# PD_Sche.net
KiCad netlist of a schematic drawn in Altium Designer
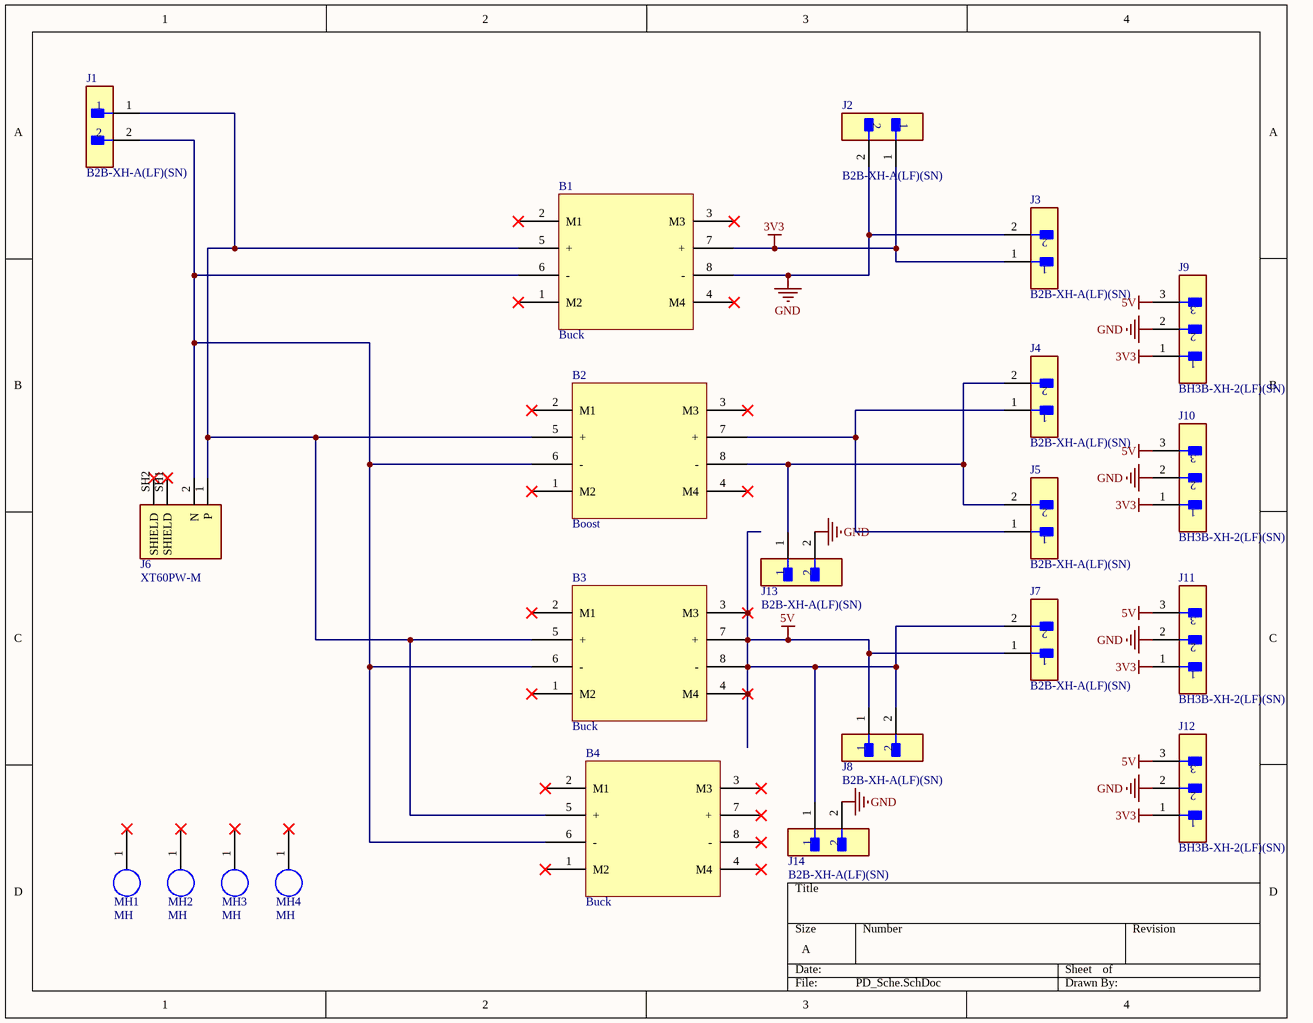
[diagram p0: PD_Sche.SchDoc]

(export (version "E")
  (design (tool "Eeschema 10.0.6"))
  (components
    (comp (ref "B1") (value "Buck") (footprint "Buck") (libsource (lib "PD_sym") (part "Buck")))
    (comp (ref "B2") (value "Boost") (footprint "Boost") (libsource (lib "PD_sym") (part "Boost")))
    (comp (ref "B3") (value "Buck") (footprint "Buck") (libsource (lib "PD_sym") (part "Buck")))
    (comp (ref "B4") (value "Buck") (footprint "Buck") (libsource (lib "PD_sym") (part "Buck")))
    (comp (ref "J1")
      (value "B2B-XH-A(LF)(SN)")
      (footprint "FP-B2B-XH-A_LF_SN-MFG")
      (description "CONN HEADER VERT 2POS 2.5MM")
      (libsource (lib "") (part "3bc925449376181038e59eaffc5286c_2"))
    )
    (comp (ref "J2")
      (value "B2B-XH-A(LF)(SN)")
      (footprint "FP-B2B-XH-A_LF_SN-MFG")
      (description "CONN HEADER VERT 2POS 2.5MM")
      (libsource (lib "") (part "3bc925449376181038e59eaffc5286c_3"))
    )
    (comp (ref "J3")
      (value "B2B-XH-A(LF)(SN)")
      (footprint "FP-B2B-XH-A_LF_SN-MFG")
      (description "CONN HEADER VERT 2POS 2.5MM")
      (libsource (lib "Altium Content Vault") (part "3bc925449376181038e59eaffc5286c"))
    )
    (comp (ref "J4")
      (value "B2B-XH-A(LF)(SN)")
      (footprint "FP-B2B-XH-A_LF_SN-MFG")
      (description "CONN HEADER VERT 2POS 2.5MM")
      (libsource (lib "Altium Content Vault") (part "3bc925449376181038e59eaffc5286c"))
    )
    (comp (ref "J5")
      (value "B2B-XH-A(LF)(SN)")
      (footprint "FP-B2B-XH-A_LF_SN-MFG")
      (description "CONN HEADER VERT 2POS 2.5MM")
      (libsource (lib "Altium Content Vault") (part "3bc925449376181038e59eaffc5286c"))
    )
    (comp (ref "J6")
      (value "XT60PW-M")
      (footprint "AMASS_XT60PW-M")
      (description "Socket, DC supply, male, PIN: 2")
      (fields (field (name "MF") "AMASS"))
      (libsource (lib "PD_sym") (part "XT60PW-M"))
    )
    (comp (ref "J7")
      (value "B2B-XH-A(LF)(SN)")
      (footprint "FP-B2B-XH-A_LF_SN-MFG")
      (description "CONN HEADER VERT 2POS 2.5MM")
      (libsource (lib "Altium Content Vault") (part "3bc925449376181038e59eaffc5286c"))
    )
    (comp (ref "J8")
      (value "B2B-XH-A(LF)(SN)")
      (footprint "FP-B2B-XH-A_LF_SN-MFG")
      (description "CONN HEADER VERT 2POS 2.5MM")
      (libsource (lib "") (part "3bc925449376181038e59eaffc5286c_1"))
    )
    (comp (ref "J9")
      (value "BH3B-XH-2(LF)(SN)")
      (footprint "FP-BH3B-XH-2_LF_SN-MFG")
      (description "CONN HEADER VERT 3POS 2.5MM")
      (libsource (lib "Altium Content Vault") (part "0d3f023dd272f625e17a2be33dea85f"))
    )
    (comp (ref "J10")
      (value "BH3B-XH-2(LF)(SN)")
      (footprint "FP-BH3B-XH-2_LF_SN-MFG")
      (description "CONN HEADER VERT 3POS 2.5MM")
      (libsource (lib "Altium Content Vault") (part "0d3f023dd272f625e17a2be33dea85f"))
    )
    (comp (ref "J11")
      (value "BH3B-XH-2(LF)(SN)")
      (footprint "FP-BH3B-XH-2_LF_SN-MFG")
      (description "CONN HEADER VERT 3POS 2.5MM")
      (libsource (lib "Altium Content Vault") (part "0d3f023dd272f625e17a2be33dea85f"))
    )
    (comp (ref "J12")
      (value "BH3B-XH-2(LF)(SN)")
      (footprint "FP-BH3B-XH-2_LF_SN-MFG")
      (description "CONN HEADER VERT 3POS 2.5MM")
      (libsource (lib "Altium Content Vault") (part "0d3f023dd272f625e17a2be33dea85f"))
    )
    (comp (ref "J13")
      (value "B2B-XH-A(LF)(SN)")
      (footprint "FP-B2B-XH-A_LF_SN-MFG")
      (description "CONN HEADER VERT 2POS 2.5MM")
      (libsource (lib "") (part "3bc925449376181038e59eaffc5286c_1"))
    )
    (comp (ref "J14")
      (value "B2B-XH-A(LF)(SN)")
      (footprint "FP-B2B-XH-A_LF_SN-MFG")
      (description "CONN HEADER VERT 2POS 2.5MM")
      (libsource (lib "") (part "3bc925449376181038e59eaffc5286c_1"))
    )
    (comp (ref "MH1") (value "MH") (footprint "MH") (libsource (lib "PD_sym") (part "MH")))
    (comp (ref "MH2") (value "MH") (footprint "MH") (libsource (lib "PD_sym") (part "MH")))
    (comp (ref "MH3") (value "MH") (footprint "MH") (libsource (lib "PD_sym") (part "MH")))
    (comp (ref "MH4") (value "MH") (footprint "MH") (libsource (lib "PD_sym") (part "MH")))
  )
  (nets
    (net (code "1") (name "3V3") (class "Default")
      (node (ref "B1") (pin "7") (pinfunction "+_7") (pintype "passive"))
      (node (ref "J10") (pin "1") (pinfunction "1_1") (pintype "passive"))
      (node (ref "J11") (pin "1") (pinfunction "1_1") (pintype "passive"))
      (node (ref "J12") (pin "1") (pinfunction "1_1") (pintype "passive"))
      (node (ref "J2") (pin "1") (pinfunction "1_1") (pintype "passive"))
      (node (ref "J3") (pin "1") (pinfunction "1_1") (pintype "passive"))
      (node (ref "J9") (pin "1") (pinfunction "1_1") (pintype "passive"))
    )
    (net (code "2") (name "5V") (class "Default")
      (node (ref "B3") (pin "3") (pinfunction "M3_3") (pintype "passive"))
      (node (ref "B3") (pin "4") (pinfunction "M4_4") (pintype "passive"))
      (node (ref "B3") (pin "7") (pinfunction "+_7") (pintype "passive"))
      (node (ref "B3") (pin "8") (pinfunction "-_8") (pintype "passive"))
      (node (ref "J10") (pin "3") (pinfunction "3_3") (pintype "passive"))
      (node (ref "J11") (pin "3") (pinfunction "3_3") (pintype "passive"))
      (node (ref "J12") (pin "3") (pinfunction "3_3") (pintype "passive"))
      (node (ref "J14") (pin "1") (pinfunction "1_1") (pintype "passive"))
      (node (ref "J7") (pin "1") (pinfunction "1_1") (pintype "passive"))
      (node (ref "J7") (pin "2") (pinfunction "2_2") (pintype "passive"))
      (node (ref "J8") (pin "1") (pinfunction "1_1") (pintype "passive"))
      (node (ref "J8") (pin "2") (pinfunction "2_2") (pintype "passive"))
      (node (ref "J9") (pin "3") (pinfunction "3_3") (pintype "passive"))
    )
    (net (code "3") (name "GND") (class "Default")
      (node (ref "B1") (pin "8") (pinfunction "-_8") (pintype "passive"))
      (node (ref "J10") (pin "2") (pinfunction "2_2") (pintype "passive"))
      (node (ref "J11") (pin "2") (pinfunction "2_2") (pintype "passive"))
      (node (ref "J12") (pin "2") (pinfunction "2_2") (pintype "passive"))
      (node (ref "J13") (pin "2") (pinfunction "2_2") (pintype "passive"))
      (node (ref "J14") (pin "2") (pinfunction "2_2") (pintype "passive"))
      (node (ref "J2") (pin "2") (pinfunction "2_2") (pintype "passive"))
      (node (ref "J3") (pin "2") (pinfunction "2_2") (pintype "passive"))
      (node (ref "J9") (pin "2") (pinfunction "2_2") (pintype "passive"))
    )
    (net (code "4") (name "Net-(B2-+-Pad7)") (class "Default")
      (node (ref "B2") (pin "7") (pinfunction "+_7") (pintype "passive"))
      (node (ref "J4") (pin "1") (pinfunction "1_1") (pintype "passive"))
      (node (ref "J5") (pin "1") (pinfunction "1_1") (pintype "passive"))
    )
    (net (code "5") (name "Net-(B2---Pad8)") (class "Default")
      (node (ref "B2") (pin "8") (pinfunction "-_8") (pintype "passive"))
      (node (ref "J13") (pin "1") (pinfunction "1_1") (pintype "passive"))
      (node (ref "J4") (pin "2") (pinfunction "2_2") (pintype "passive"))
      (node (ref "J5") (pin "2") (pinfunction "2_2") (pintype "passive"))
    )
    (net (code "6") (name "Net-(J6-N)") (class "Default")
      (node (ref "B1") (pin "6") (pinfunction "-_6") (pintype "passive"))
      (node (ref "B2") (pin "6") (pinfunction "-_6") (pintype "passive"))
      (node (ref "B3") (pin "6") (pinfunction "-_6") (pintype "passive"))
      (node (ref "B4") (pin "6") (pinfunction "-_6") (pintype "passive"))
      (node (ref "J1") (pin "2") (pinfunction "2_2") (pintype "passive"))
      (node (ref "J6") (pin "2") (pinfunction "N_2") (pintype "passive"))
    )
    (net (code "7") (name "Net-(J6-P)") (class "Default")
      (node (ref "B1") (pin "5") (pinfunction "+_5") (pintype "passive"))
      (node (ref "B2") (pin "5") (pinfunction "+_5") (pintype "passive"))
      (node (ref "B3") (pin "5") (pinfunction "+_5") (pintype "passive"))
      (node (ref "B4") (pin "5") (pinfunction "+_5") (pintype "passive"))
      (node (ref "J1") (pin "1") (pinfunction "1_1") (pintype "passive"))
      (node (ref "J6") (pin "1") (pinfunction "P_1") (pintype "passive"))
    )
    (net (code "8") (name "unconnected-(B1-M1-Pad2)") (class "Default")
      (node (ref "B1") (pin "2") (pinfunction "M1_2") (pintype "passive+no_connect"))
    )
    (net (code "9") (name "unconnected-(B1-M2-Pad1)") (class "Default")
      (node (ref "B1") (pin "1") (pinfunction "M2_1") (pintype "passive+no_connect"))
    )
    (net (code "10") (name "unconnected-(B1-M3-Pad3)") (class "Default")
      (node (ref "B1") (pin "3") (pinfunction "M3_3") (pintype "passive+no_connect"))
    )
    (net (code "11") (name "unconnected-(B1-M4-Pad4)") (class "Default")
      (node (ref "B1") (pin "4") (pinfunction "M4_4") (pintype "passive+no_connect"))
    )
    (net (code "12") (name "unconnected-(B2-M1-Pad2)") (class "Default")
      (node (ref "B2") (pin "2") (pinfunction "M1_2") (pintype "passive+no_connect"))
    )
    (net (code "13") (name "unconnected-(B2-M2-Pad1)") (class "Default")
      (node (ref "B2") (pin "1") (pinfunction "M2_1") (pintype "passive+no_connect"))
    )
    (net (code "14") (name "unconnected-(B2-M3-Pad3)") (class "Default")
      (node (ref "B2") (pin "3") (pinfunction "M3_3") (pintype "passive+no_connect"))
    )
    (net (code "15") (name "unconnected-(B2-M4-Pad4)") (class "Default")
      (node (ref "B2") (pin "4") (pinfunction "M4_4") (pintype "passive+no_connect"))
    )
    (net (code "16") (name "unconnected-(B3-M1-Pad2)") (class "Default")
      (node (ref "B3") (pin "2") (pinfunction "M1_2") (pintype "passive+no_connect"))
    )
    (net (code "17") (name "unconnected-(B3-M2-Pad1)") (class "Default")
      (node (ref "B3") (pin "1") (pinfunction "M2_1") (pintype "passive+no_connect"))
    )
    (net (code "18") (name "unconnected-(B4-+-Pad7)") (class "Default")
      (node (ref "B4") (pin "7") (pinfunction "+_7") (pintype "passive+no_connect"))
    )
    (net (code "19") (name "unconnected-(B4---Pad8)") (class "Default")
      (node (ref "B4") (pin "8") (pinfunction "-_8") (pintype "passive+no_connect"))
    )
    (net (code "20") (name "unconnected-(B4-M1-Pad2)") (class "Default")
      (node (ref "B4") (pin "2") (pinfunction "M1_2") (pintype "passive+no_connect"))
    )
    (net (code "21") (name "unconnected-(B4-M2-Pad1)") (class "Default")
      (node (ref "B4") (pin "1") (pinfunction "M2_1") (pintype "passive+no_connect"))
    )
    (net (code "22") (name "unconnected-(B4-M3-Pad3)") (class "Default")
      (node (ref "B4") (pin "3") (pinfunction "M3_3") (pintype "passive+no_connect"))
    )
    (net (code "23") (name "unconnected-(B4-M4-Pad4)") (class "Default")
      (node (ref "B4") (pin "4") (pinfunction "M4_4") (pintype "passive+no_connect"))
    )
    (net (code "24") (name "unconnected-(J6-SHIELD-PadSH1)") (class "Default")
      (node (ref "J6") (pin "SH1") (pinfunction "SHIELD_SH1") (pintype "passive+no_connect"))
    )
    (net (code "25") (name "unconnected-(J6-SHIELD-PadSH2)") (class "Default")
      (node (ref "J6") (pin "SH2") (pinfunction "SHIELD_SH2") (pintype "passive+no_connect"))
    )
    (net (code "26") (name "unconnected-(MH1-Pad1)") (class "Default")
      (node (ref "MH1") (pin "1") (pinfunction "1_1") (pintype "passive+no_connect"))
    )
    (net (code "27") (name "unconnected-(MH2-Pad1)") (class "Default")
      (node (ref "MH2") (pin "1") (pinfunction "1_1") (pintype "passive+no_connect"))
    )
    (net (code "28") (name "unconnected-(MH3-Pad1)") (class "Default")
      (node (ref "MH3") (pin "1") (pinfunction "1_1") (pintype "passive+no_connect"))
    )
    (net (code "29") (name "unconnected-(MH4-Pad1)") (class "Default")
      (node (ref "MH4") (pin "1") (pinfunction "1_1") (pintype "passive+no_connect"))
    )
  )
)
